# Sheet1.net
KiCad netlist of a schematic drawn in Altium Designer
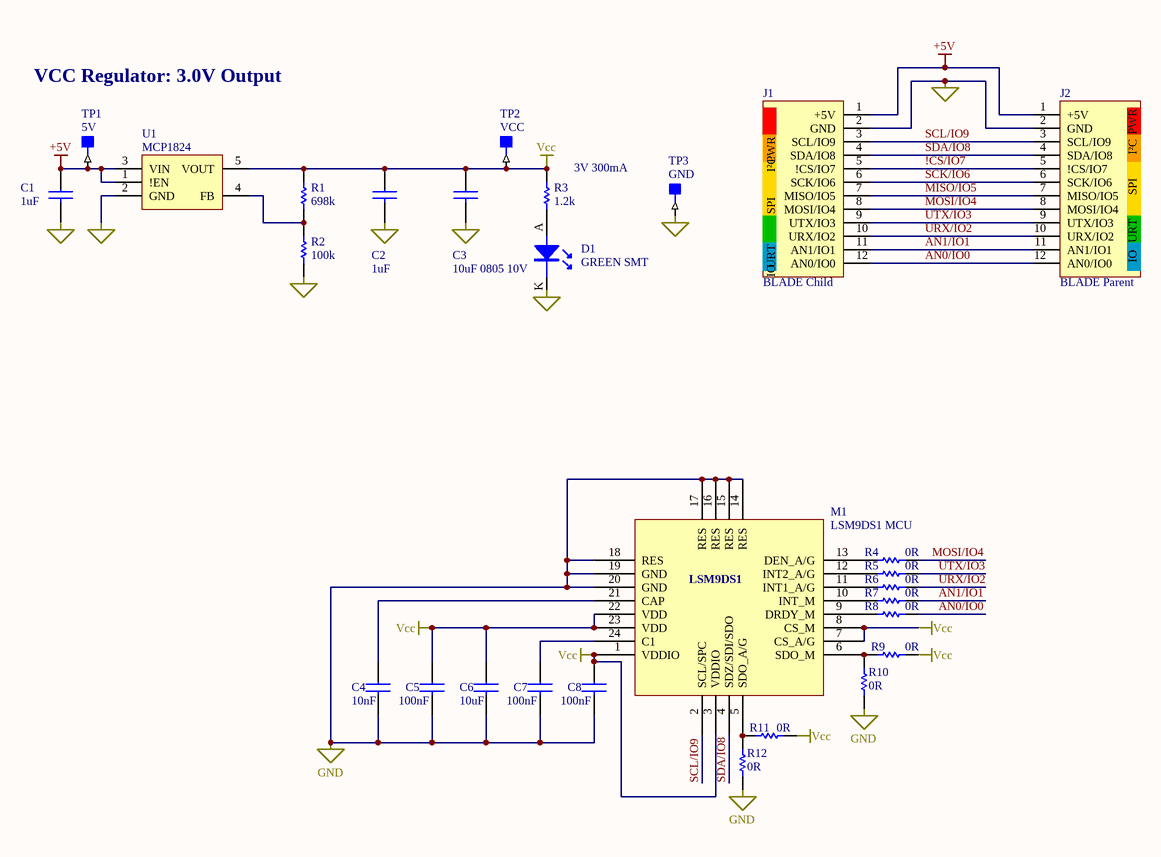
[diagram p0: Sheet1.SchDoc]

(export (version "E")
  (design (tool "Eeschema 10.0.6"))
  (components
    (comp (ref "C1")
      (value "1uF")
      (footprint "0603")
      (fields
        (field (name "4. DIGI-KEY PART NUMBER") "587-1251-2-ND")
        (field (name "3. MANUFACTURER PART NUMBER") "EMK107BJ105KA-T")
        (field (name "5. INTERNAL PART NUMBER") "100009")
        (field (name "7. MODIFIED BY") "JRL")
      )
      (libsource (lib "Blackline Master Schematic Library") (part "CAPACITOR NON-POLARIZED"))
    )
    (comp (ref "C2")
      (value "1uF")
      (footprint "0603")
      (fields
        (field (name "4. DIGI-KEY PART NUMBER") "587-1251-2-ND")
        (field (name "3. MANUFACTURER PART NUMBER") "EMK107BJ105KA-T")
        (field (name "5. INTERNAL PART NUMBER") "100009")
        (field (name "7. MODIFIED BY") "JRL")
      )
      (libsource (lib "Blackline Master Schematic Library") (part "CAPACITOR NON-POLARIZED"))
    )
    (comp (ref "C3")
      (value "10uF 0805 10V")
      (footprint "0805")
      (fields
        (field (name "4. DIGI-KEY PART NUMBER") "587-1300-1-ND")
        (field (name "3. MANUFACTURER PART NUMBER") "LMK212BJ106KG-T")
        (field (name "5. INTERNAL PART NUMBER") "100006")
        (field (name "7. MODIFIED BY") "JRL")
      )
      (libsource (lib "Blackline Master Schematic Library") (part "CAPACITOR NON-POLARIZED"))
    )
    (comp (ref "C4")
      (value "10nF")
      (footprint "0603")
      (fields (field (name "7. MODIFIED BY") "*"))
      (libsource (lib "Altium Example Master Schematic Library") (part "CAPACITOR NON-POLARIZED"))
    )
    (comp (ref "C5")
      (value "100nF")
      (footprint "0603")
      (fields (field (name "7. MODIFIED BY") "*"))
      (libsource (lib "Altium Example Master Schematic Library") (part "CAPACITOR NON-POLARIZED"))
    )
    (comp (ref "C6")
      (value "10uF")
      (footprint "0603")
      (fields (field (name "7. MODIFIED BY") "*"))
      (libsource (lib "Altium Example Master Schematic Library") (part "CAPACITOR NON-POLARIZED"))
    )
    (comp (ref "C7")
      (value "100nF")
      (footprint "0603")
      (fields (field (name "7. MODIFIED BY") "*"))
      (libsource (lib "Altium Example Master Schematic Library") (part "CAPACITOR NON-POLARIZED"))
    )
    (comp (ref "C8")
      (value "100nF")
      (footprint "0603")
      (fields (field (name "7. MODIFIED BY") "*"))
      (libsource (lib "Altium Example Master Schematic Library") (part "CAPACITOR NON-POLARIZED"))
    )
    (comp (ref "D1")
      (value "GREEN SMT")
      (footprint "0603 AK")
      (description "LED")
      (fields
        (field (name "3. MANUFACTURER PART NUMBER") "LTST-C190GKT")
        (field (name "4. DIGI-KEY PART NUMBER") "160-1183-1-ND")
        (field (name "7. MODIFIED BY") "JRL")
      )
      (libsource (lib "*") (part "LED T1-3/4"))
    )
    (comp (ref "J1")
      (value "BLADE Child")
      (footprint "HDR1X12 ENGENUICS CHILD")
      (fields
        (field (name "3. MANUFACTURER PART NUMBER") "68016-412HLF")
        (field (name "4. DIGI-KEY PART NUMBER") "609-3330-ND")
        (field (name "5. INTERNAL PART NUMBER") "100021")
        (field (name "7. MODIFIED BY") "JRL")
      )
      (libsource (lib "Engenuics Master Schematic Library") (part "CONN ENGENUICS BLADE CHILD"))
    )
    (comp (ref "J2")
      (value "BLADE Parent")
      (footprint "HDR1X12 ENGENUICS PARENT")
      (fields
        (field (name "3. MANUFACTURER PART NUMBER") "PPTC121LGBN-RC")
        (field (name "4. DIGI-KEY PART NUMBER") "S5448-ND")
        (field (name "5. INTERNAL PART NUMBER") "100031")
        (field (name "7. MODIFIED BY") "JRL")
      )
      (libsource (lib "Engenuics Master Schematic Library") (part "CONN ENGENUICS BLADE PARENT"))
    )
    (comp (ref "M1")
      (value "LSM9DS1 MCU")
      (footprint "LSM9DS3")
      (fields
        (field (name "DIGI-KEY PART NUMBER") "497-14946-1-ND")
        (field (name "MANUFACTURER PART NUMBER") "LSM9DS1TR")
        (field (name "MANUFACTURER") "STMicroelectronics")
        (field (name "MODIFIED BY") "Bud Wandinger")
      )
      (libsource (lib "Engenuics Blade Schematic Library") (part "LSM9DS1"))
    )
    (comp (ref "R1")
      (value "698k")
      (footprint "0603")
      (fields
        (field (name "4. DIGI-KEY PART NUMBER") "311-698KHRCT-ND")
        (field (name "3. MANUFACTURER PART NUMBER") "RC0603FR-07698KL")
        (field (name "5. INTERNAL PART NUMBER") "100087")
        (field (name "7. MODIFIED BY") "JRL")
      )
      (libsource (lib "Blackline Master Schematic Library") (part "RESISTOR"))
    )
    (comp (ref "R2")
      (value "100k")
      (footprint "0603")
      (fields
        (field (name "4. DIGI-KEY PART NUMBER") "RHM100KGCT-ND")
        (field (name "3. MANUFACTURER PART NUMBER") "MCR03EZPJ104")
        (field (name "5. INTERNAL PART NUMBER") "100078")
        (field (name "7. MODIFIED BY") "JRL")
      )
      (libsource (lib "Blackline Master Schematic Library") (part "RESISTOR"))
    )
    (comp (ref "R3")
      (value "1.2k")
      (footprint "0603")
      (fields
        (field (name "4. DIGI-KEY PART NUMBER") "RHM1.2KGCT-ND")
        (field (name "3. MANUFACTURER PART NUMBER") "MCR03EZPJ122")
        (field (name "5. INTERNAL PART NUMBER") "100076")
        (field (name "7. MODIFIED BY") "JRL")
      )
      (libsource (lib "Blackline Master Schematic Library") (part "RESISTOR"))
    )
    (comp (ref "R4")
      (value "0R")
      (footprint "0603")
      (fields (field (name "7. MODIFIED BY") "*"))
      (libsource (lib "Altium Example Master Schematic Library") (part "RESISTOR"))
    )
    (comp (ref "R5")
      (value "0R")
      (footprint "0603")
      (fields (field (name "7. MODIFIED BY") "*"))
      (libsource (lib "Altium Example Master Schematic Library") (part "RESISTOR"))
    )
    (comp (ref "R6")
      (value "0R")
      (footprint "0603")
      (fields (field (name "7. MODIFIED BY") "*"))
      (libsource (lib "Altium Example Master Schematic Library") (part "RESISTOR"))
    )
    (comp (ref "R7")
      (value "0R")
      (footprint "0603")
      (fields (field (name "7. MODIFIED BY") "*"))
      (libsource (lib "Altium Example Master Schematic Library") (part "RESISTOR"))
    )
    (comp (ref "R8")
      (value "0R")
      (footprint "0603")
      (fields (field (name "7. MODIFIED BY") "*"))
      (libsource (lib "Altium Example Master Schematic Library") (part "RESISTOR"))
    )
    (comp (ref "R9")
      (value "0R")
      (footprint "0603")
      (fields (field (name "7. MODIFIED BY") "*"))
      (libsource (lib "Altium Example Master Schematic Library") (part "RESISTOR"))
    )
    (comp (ref "R10")
      (value "0R")
      (footprint "0603")
      (fields (field (name "7. MODIFIED BY") "*"))
      (libsource (lib "Altium Example Master Schematic Library") (part "RESISTOR"))
    )
    (comp (ref "R11")
      (value "0R")
      (footprint "0603")
      (fields (field (name "7. MODIFIED BY") "*"))
      (libsource (lib "Altium Example Master Schematic Library") (part "RESISTOR"))
    )
    (comp (ref "R12")
      (value "0R")
      (footprint "0603")
      (fields (field (name "7. MODIFIED BY") "*"))
      (libsource (lib "Altium Example Master Schematic Library") (part "RESISTOR"))
    )
    (comp (ref "TP1")
      (value "5V")
      (footprint "TEST POINT SMT")
      (fields (field (name "7. MODIFIED BY") "JRL"))
      (libsource (lib "Blackline Master Schematic Library") (part "TEST POINT SMT"))
    )
    (comp (ref "TP2")
      (value "VCC")
      (footprint "TEST POINT SMT")
      (fields (field (name "7. MODIFIED BY") "JRL"))
      (libsource (lib "Blackline Master Schematic Library") (part "TEST POINT SMT"))
    )
    (comp (ref "TP3")
      (value "GND")
      (footprint "TEST POINT SMT")
      (fields (field (name "7. MODIFIED BY") "JRL"))
      (libsource (lib "Blackline Master Schematic Library") (part "TEST POINT SMT"))
    )
    (comp (ref "U1")
      (value "MCP1824")
      (footprint "SOT23-5")
      (fields
        (field (name "3. MANUFACTURER PART NUMBER") "MCP1824T-ADJE/OT")
        (field (name "4. DIGI-KEY PART NUMBER") "MCP1824T-ADJE/OTCT-ND")
        (field (name "5. INTERNAL PART NUMBER") "100049")
        (field (name "7. MODIFIED BY") "JRL")
      )
      (libsource (lib "Device") (part "VREG MCP1824"))
    )
  )
  (nets
    (net (code "1") (name "+5V") (class "Default")
      (node (ref "C1") (pin "1") (pinfunction "1_1") (pintype "passive"))
      (node (ref "J1") (pin "1") (pinfunction "+5V_1") (pintype "passive"))
      (node (ref "J2") (pin "1") (pinfunction "+5V_1") (pintype "passive"))
      (node (ref "TP1") (pin "1") (pinfunction "1_1") (pintype "input"))
      (node (ref "U1") (pin "1") (pinfunction "!EN_1") (pintype "passive"))
      (node (ref "U1") (pin "3") (pinfunction "VIN_3") (pintype "passive"))
    )
    (net (code "2") (name "/!CS{slash}IO7") (class "Default")
      (node (ref "J1") (pin "5") (pinfunction "!CS/IO7_5") (pintype "passive"))
      (node (ref "J2") (pin "5") (pinfunction "!CS/IO7_5") (pintype "passive"))
    )
    (net (code "3") (name "/AN0{slash}IO0") (class "Default")
      (node (ref "J1") (pin "12") (pinfunction "AN0/IO0_12") (pintype "passive"))
      (node (ref "J2") (pin "12") (pinfunction "AN0/IO0_12") (pintype "passive"))
      (node (ref "R8") (pin "2") (pinfunction "2_2") (pintype "passive"))
    )
    (net (code "4") (name "/AN1{slash}IO1") (class "Default")
      (node (ref "J1") (pin "11") (pinfunction "AN1/IO1_11") (pintype "passive"))
      (node (ref "J2") (pin "11") (pinfunction "AN1/IO1_11") (pintype "passive"))
      (node (ref "R7") (pin "2") (pinfunction "2_2") (pintype "passive"))
    )
    (net (code "5") (name "/MISO{slash}IO5") (class "Default")
      (node (ref "J1") (pin "7") (pinfunction "MISO/IO5_7") (pintype "passive"))
      (node (ref "J2") (pin "7") (pinfunction "MISO/IO5_7") (pintype "passive"))
    )
    (net (code "6") (name "/MOSI{slash}IO4") (class "Default")
      (node (ref "J1") (pin "8") (pinfunction "MOSI/IO4_8") (pintype "passive"))
      (node (ref "J2") (pin "8") (pinfunction "MOSI/IO4_8") (pintype "passive"))
      (node (ref "R4") (pin "2") (pinfunction "2_2") (pintype "passive"))
    )
    (net (code "7") (name "/SCK{slash}IO6") (class "Default")
      (node (ref "J1") (pin "6") (pinfunction "SCK/IO6_6") (pintype "passive"))
      (node (ref "J2") (pin "6") (pinfunction "SCK/IO6_6") (pintype "passive"))
    )
    (net (code "8") (name "/SCL{slash}IO9") (class "Default")
      (node (ref "J1") (pin "3") (pinfunction "SCL/IO9_3") (pintype "passive"))
      (node (ref "J2") (pin "3") (pinfunction "SCL/IO9_3") (pintype "passive"))
      (node (ref "M1") (pin "2") (pinfunction "SCL/SPC_2") (pintype "passive"))
    )
    (net (code "9") (name "/SDA{slash}IO8") (class "Default")
      (node (ref "J1") (pin "4") (pinfunction "SDA/IO8_4") (pintype "passive"))
      (node (ref "J2") (pin "4") (pinfunction "SDA/IO8_4") (pintype "passive"))
      (node (ref "M1") (pin "4") (pinfunction "SDZ/SDI/SDO_4") (pintype "passive"))
    )
    (net (code "10") (name "/URX{slash}IO2") (class "Default")
      (node (ref "J1") (pin "10") (pinfunction "URX/IO2_10") (pintype "passive"))
      (node (ref "J2") (pin "10") (pinfunction "URX/IO2_10") (pintype "passive"))
      (node (ref "R6") (pin "2") (pinfunction "2_2") (pintype "passive"))
    )
    (net (code "11") (name "/UTX{slash}IO3") (class "Default")
      (node (ref "J1") (pin "9") (pinfunction "UTX/IO3_9") (pintype "passive"))
      (node (ref "J2") (pin "9") (pinfunction "UTX/IO3_9") (pintype "passive"))
      (node (ref "R5") (pin "2") (pinfunction "2_2") (pintype "passive"))
    )
    (net (code "12") (name "GND") (class "Default")
      (node (ref "C1") (pin "2") (pinfunction "2_2") (pintype "passive"))
      (node (ref "C2") (pin "2") (pinfunction "2_2") (pintype "passive"))
      (node (ref "C3") (pin "2") (pinfunction "2_2") (pintype "passive"))
      (node (ref "C4") (pin "2") (pinfunction "2_2") (pintype "passive"))
      (node (ref "C5") (pin "2") (pinfunction "2_2") (pintype "passive"))
      (node (ref "C6") (pin "2") (pinfunction "2_2") (pintype "passive"))
      (node (ref "C7") (pin "2") (pinfunction "2_2") (pintype "passive"))
      (node (ref "C8") (pin "2") (pinfunction "2_2") (pintype "passive"))
      (node (ref "D1") (pin "K") (pinfunction "K1_K") (pintype "passive"))
      (node (ref "J1") (pin "2") (pinfunction "GND_2") (pintype "passive"))
      (node (ref "J2") (pin "2") (pinfunction "GND_2") (pintype "passive"))
      (node (ref "M1") (pin "14") (pinfunction "RES_14") (pintype "passive"))
      (node (ref "M1") (pin "15") (pinfunction "RES_15") (pintype "passive"))
      (node (ref "M1") (pin "16") (pinfunction "RES_16") (pintype "passive"))
      (node (ref "M1") (pin "17") (pinfunction "RES_17") (pintype "passive"))
      (node (ref "M1") (pin "18") (pinfunction "RES_18") (pintype "passive"))
      (node (ref "M1") (pin "19") (pinfunction "GND_19") (pintype "passive"))
      (node (ref "M1") (pin "20") (pinfunction "GND_20") (pintype "passive"))
      (node (ref "R10") (pin "1") (pinfunction "1_1") (pintype "passive"))
      (node (ref "R12") (pin "1") (pinfunction "1_1") (pintype "passive"))
      (node (ref "R2") (pin "2") (pinfunction "2_2") (pintype "passive"))
      (node (ref "TP3") (pin "1") (pinfunction "1_1") (pintype "input"))
      (node (ref "U1") (pin "2") (pinfunction "GND_2") (pintype "passive"))
    )
    (net (code "13") (name "Net-(D1-A1)") (class "Default")
      (node (ref "D1") (pin "A") (pinfunction "A1_A") (pintype "passive"))
      (node (ref "R3") (pin "1") (pinfunction "1_1") (pintype "passive"))
    )
    (net (code "14") (name "Net-(M1-C1)") (class "Default")
      (node (ref "C7") (pin "1") (pinfunction "1_1") (pintype "passive"))
      (node (ref "M1") (pin "24") (pinfunction "C1_24") (pintype "passive"))
    )
    (net (code "15") (name "Net-(M1-CAP)") (class "Default")
      (node (ref "C4") (pin "1") (pinfunction "1_1") (pintype "passive"))
      (node (ref "M1") (pin "21") (pinfunction "CAP_21") (pintype "passive"))
    )
    (net (code "16") (name "Net-(M1-DEN_A{slash}G)") (class "Default")
      (node (ref "M1") (pin "13") (pinfunction "DEN_A/G_13") (pintype "passive"))
      (node (ref "R4") (pin "1") (pinfunction "1_1") (pintype "passive"))
    )
    (net (code "17") (name "Net-(M1-DRDY_M)") (class "Default")
      (node (ref "M1") (pin "9") (pinfunction "DRDY_M_9") (pintype "passive"))
      (node (ref "R8") (pin "1") (pinfunction "1_1") (pintype "passive"))
    )
    (net (code "18") (name "Net-(M1-INT1_A{slash}G)") (class "Default")
      (node (ref "M1") (pin "11") (pinfunction "INT1_A/G_11") (pintype "passive"))
      (node (ref "R6") (pin "1") (pinfunction "1_1") (pintype "passive"))
    )
    (net (code "19") (name "Net-(M1-INT2_A{slash}G)") (class "Default")
      (node (ref "M1") (pin "12") (pinfunction "INT2_A/G_12") (pintype "passive"))
      (node (ref "R5") (pin "1") (pinfunction "1_1") (pintype "passive"))
    )
    (net (code "20") (name "Net-(M1-INT_M)") (class "Default")
      (node (ref "M1") (pin "10") (pinfunction "INT_M_10") (pintype "passive"))
      (node (ref "R7") (pin "1") (pinfunction "1_1") (pintype "passive"))
    )
    (net (code "21") (name "Net-(M1-SDO_A{slash}G)") (class "Default")
      (node (ref "M1") (pin "5") (pinfunction "SDO_A/G_5") (pintype "passive"))
      (node (ref "R11") (pin "2") (pinfunction "2_2") (pintype "passive"))
      (node (ref "R12") (pin "2") (pinfunction "2_2") (pintype "passive"))
    )
    (net (code "22") (name "Net-(M1-SDO_M)") (class "Default")
      (node (ref "M1") (pin "6") (pinfunction "SDO_M_6") (pintype "passive"))
      (node (ref "R10") (pin "2") (pinfunction "2_2") (pintype "passive"))
      (node (ref "R9") (pin "1") (pinfunction "1_1") (pintype "passive"))
    )
    (net (code "23") (name "Net-(U1-FB)") (class "Default")
      (node (ref "R1") (pin "1") (pinfunction "1_1") (pintype "passive"))
      (node (ref "R2") (pin "1") (pinfunction "1_1") (pintype "passive"))
      (node (ref "U1") (pin "4") (pinfunction "FB_4") (pintype "passive"))
    )
    (net (code "24") (name "Vcc") (class "Default")
      (node (ref "C2") (pin "1") (pinfunction "1_1") (pintype "passive"))
      (node (ref "C3") (pin "1") (pinfunction "1_1") (pintype "passive"))
      (node (ref "C5") (pin "1") (pinfunction "1_1") (pintype "passive"))
      (node (ref "C6") (pin "1") (pinfunction "1_1") (pintype "passive"))
      (node (ref "C8") (pin "1") (pinfunction "1_1") (pintype "passive"))
      (node (ref "M1") (pin "1") (pinfunction "VDDIO_1") (pintype "passive"))
      (node (ref "M1") (pin "22") (pinfunction "VDD_22") (pintype "passive"))
      (node (ref "M1") (pin "23") (pinfunction "VDD_23") (pintype "passive"))
      (node (ref "M1") (pin "3") (pinfunction "VDDIO_3") (pintype "passive"))
      (node (ref "M1") (pin "7") (pinfunction "CS_A/G_7") (pintype "passive"))
      (node (ref "M1") (pin "8") (pinfunction "CS_M_8") (pintype "passive"))
      (node (ref "R1") (pin "2") (pinfunction "2_2") (pintype "passive"))
      (node (ref "R11") (pin "1") (pinfunction "1_1") (pintype "passive"))
      (node (ref "R3") (pin "2") (pinfunction "2_2") (pintype "passive"))
      (node (ref "R9") (pin "2") (pinfunction "2_2") (pintype "passive"))
      (node (ref "TP2") (pin "1") (pinfunction "1_1") (pintype "input"))
      (node (ref "U1") (pin "5") (pinfunction "VOUT_5") (pintype "passive"))
    )
  )
)
